# Regulauta.net
KiCad netlist of a schematic drawn in EAGLE
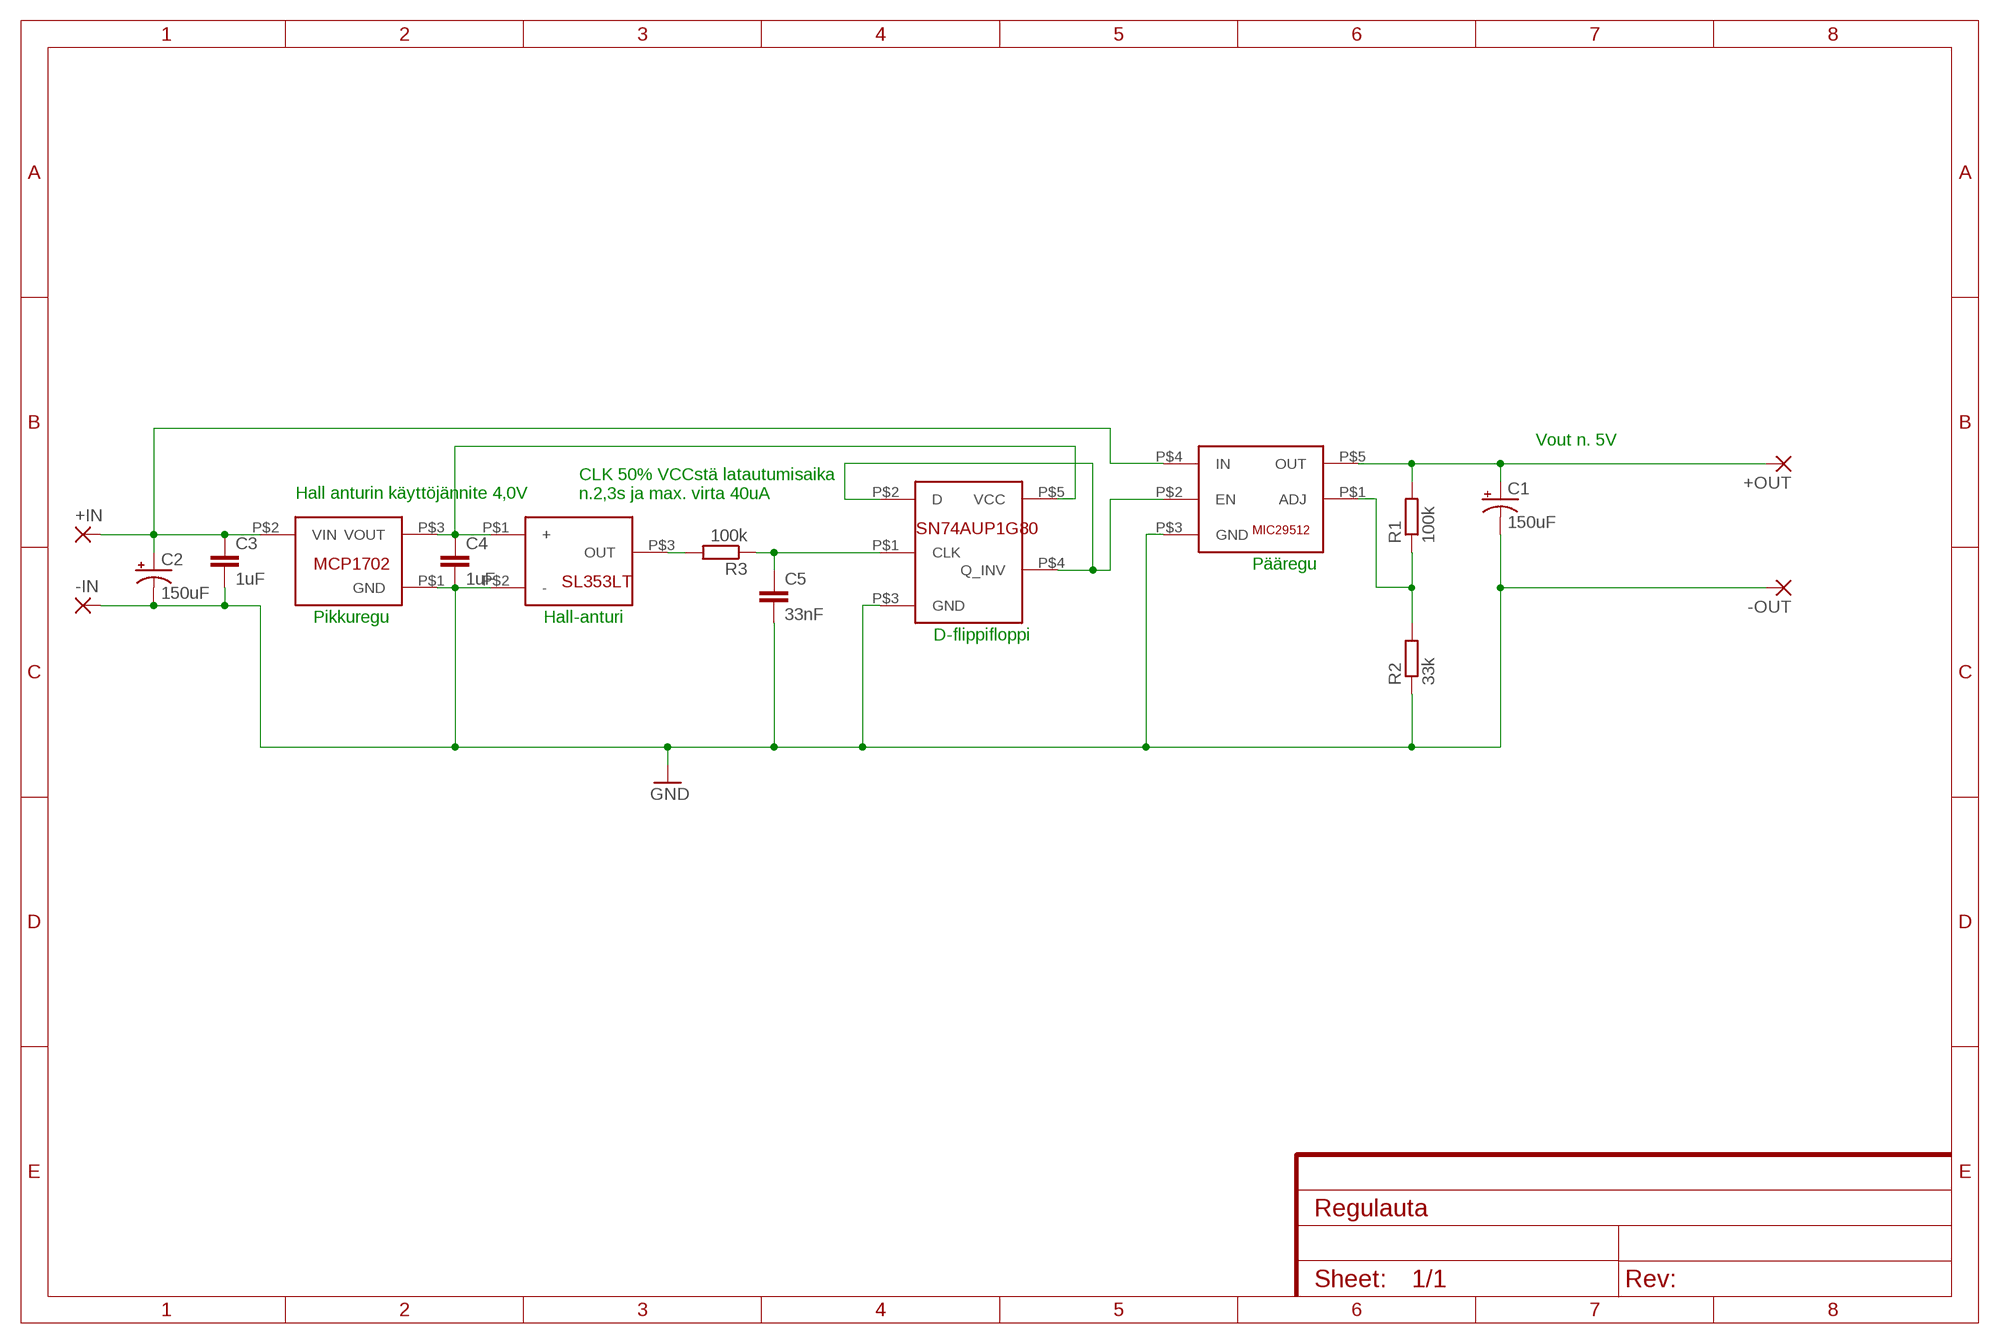
[diagram p0: schematic, sheet 1]

(export (version "E")
  (design (tool "Eeschema 10.0.6"))
  (components
    (comp (ref "+IN")
      (value "SMD5")
      (footprint "eagle-import:SMD2,54-5,08")
      (libsource (lib "eagle-import") (part "SMD5"))
    )
    (comp (ref "+OUT")
      (value "SMD5")
      (footprint "eagle-import:SMD2,54-5,08")
      (libsource (lib "eagle-import") (part "SMD5"))
    )
    (comp (ref "-IN")
      (value "SMD5")
      (footprint "eagle-import:SMD2,54-5,08")
      (libsource (lib "eagle-import") (part "SMD5"))
    )
    (comp (ref "-OUT")
      (value "SMD5")
      (footprint "eagle-import:SMD2,54-5,08")
      (libsource (lib "eagle-import") (part "SMD5"))
    )
    (comp (ref "C1")
      (value "150uF")
      (footprint "eagle-import:CPOL-RADIAL-100UF-25V")
      (libsource (lib "eagle-import") (part "CAP_POLPTH1"))
    )
    (comp (ref "C2")
      (value "150uF")
      (footprint "eagle-import:CPOL-RADIAL-100UF-25V")
      (libsource (lib "eagle-import") (part "CAP_POLPTH1"))
    )
    (comp (ref "C3")
      (value "1uF")
      (footprint "eagle-import:1206")
      (libsource (lib "eagle-import") (part "CAP1206"))
    )
    (comp (ref "C4")
      (value "1uF")
      (footprint "eagle-import:1206")
      (libsource (lib "eagle-import") (part "CAP1206"))
    )
    (comp (ref "C5")
      (value "33nF")
      (footprint "eagle-import:1206")
      (libsource (lib "eagle-import") (part "CAP1206"))
    )
    (comp (ref "R1")
      (value "100k")
      (footprint "eagle-import:R1206")
      (libsource (lib "eagle-import") (part "R-EU_R1206"))
    )
    (comp (ref "R2")
      (value "33k")
      (footprint "eagle-import:R1206")
      (libsource (lib "eagle-import") (part "R-EU_R1206"))
    )
    (comp (ref "R3")
      (value "100k")
      (footprint "eagle-import:R1206")
      (libsource (lib "eagle-import") (part "R-EU_R1206"))
    )
    (comp (ref "U$1")
      (value "SL353LT")
      (footprint "eagle-import:SL353LT")
      (libsource (lib "eagle-import") (part "SL353LT"))
    )
    (comp (ref "U$2")
      (value "MIC29512")
      (footprint "eagle-import:MIC29512")
      (libsource (lib "eagle-import") (part "MIC29512"))
    )
    (comp (ref "U$3")
      (value "SN74AUP1G80")
      (footprint "eagle-import:SN74AUP1G80")
      (libsource (lib "eagle-import") (part "SN74AUP1G80"))
    )
    (comp (ref "U$4")
      (value "MCP1702")
      (footprint "eagle-import:SL353LT")
      (libsource (lib "eagle-import") (part "MCP1702"))
    )
  )
  (nets
    (net (code "1") (name "GND") (class "Default")
      (node (ref "-IN") (pin "1") (pinfunction "P_1") (pintype "passive"))
      (node (ref "-OUT") (pin "1") (pinfunction "P_1") (pintype "passive"))
      (node (ref "C1") (pin "2") (pinfunction "-_2") (pintype "passive"))
      (node (ref "C2") (pin "2") (pinfunction "-_2") (pintype "passive"))
      (node (ref "C3") (pin "2") (pinfunction "2_2") (pintype "passive"))
      (node (ref "C4") (pin "2") (pinfunction "2_2") (pintype "passive"))
      (node (ref "C5") (pin "2") (pinfunction "2_2") (pintype "passive"))
      (node (ref "R2") (pin "1") (pinfunction "1_1") (pintype "passive"))
      (node (ref "U$1") (pin "P$2") (pinfunction "-_P$2") (pintype "bidirectional"))
      (node (ref "U$2") (pin "P$3") (pinfunction "GND_P$3") (pintype "bidirectional"))
      (node (ref "U$3") (pin "P$3") (pinfunction "GND_P$3") (pintype "bidirectional"))
      (node (ref "U$4") (pin "P$1") (pinfunction "GND_P$1") (pintype "bidirectional"))
    )
    (net (code "2") (name "Net-(+IN-P)") (class "Default")
      (node (ref "+IN") (pin "1") (pinfunction "P_1") (pintype "passive"))
      (node (ref "C2") (pin "1") (pinfunction "+_1") (pintype "passive"))
      (node (ref "C3") (pin "1") (pinfunction "1_1") (pintype "passive"))
      (node (ref "U$2") (pin "P$4") (pinfunction "IN_P$4") (pintype "bidirectional"))
      (node (ref "U$4") (pin "P$2") (pinfunction "VIN_P$2") (pintype "bidirectional"))
    )
    (net (code "3") (name "Net-(+OUT-P)") (class "Default")
      (node (ref "+OUT") (pin "1") (pinfunction "P_1") (pintype "passive"))
      (node (ref "C1") (pin "1") (pinfunction "+_1") (pintype "passive"))
      (node (ref "R1") (pin "2") (pinfunction "2_2") (pintype "passive"))
      (node (ref "U$2") (pin "P$5") (pinfunction "OUT_P$5") (pintype "bidirectional"))
    )
    (net (code "4") (name "Net-(U$1-+)") (class "Default")
      (node (ref "C4") (pin "1") (pinfunction "1_1") (pintype "passive"))
      (node (ref "U$1") (pin "P$1") (pinfunction "+_P$1") (pintype "bidirectional"))
      (node (ref "U$3") (pin "P$5") (pinfunction "VCC_P$5") (pintype "bidirectional"))
      (node (ref "U$4") (pin "P$3") (pinfunction "VOUT_P$3") (pintype "bidirectional"))
    )
    (net (code "5") (name "Net-(U$1-OUT)") (class "Default")
      (node (ref "R3") (pin "2") (pinfunction "2_2") (pintype "passive"))
      (node (ref "U$1") (pin "P$3") (pinfunction "OUT_P$3") (pintype "bidirectional"))
    )
    (net (code "6") (name "Net-(U$2-ADJ)") (class "Default")
      (node (ref "R1") (pin "1") (pinfunction "1_1") (pintype "passive"))
      (node (ref "R2") (pin "2") (pinfunction "2_2") (pintype "passive"))
      (node (ref "U$2") (pin "P$1") (pinfunction "ADJ_P$1") (pintype "bidirectional"))
    )
    (net (code "7") (name "Net-(U$2-EN)") (class "Default")
      (node (ref "U$2") (pin "P$2") (pinfunction "EN_P$2") (pintype "bidirectional"))
      (node (ref "U$3") (pin "P$2") (pinfunction "D_P$2") (pintype "bidirectional"))
      (node (ref "U$3") (pin "P$4") (pinfunction "Q_INV_P$4") (pintype "bidirectional"))
    )
    (net (code "8") (name "Net-(U$3-CLK)") (class "Default")
      (node (ref "C5") (pin "1") (pinfunction "1_1") (pintype "passive"))
      (node (ref "R3") (pin "1") (pinfunction "1_1") (pintype "passive"))
      (node (ref "U$3") (pin "P$1") (pinfunction "CLK_P$1") (pintype "bidirectional"))
    )
  )
)
